# Game_Consol_Power.net
KiCad netlist of a schematic drawn in Altium Designer
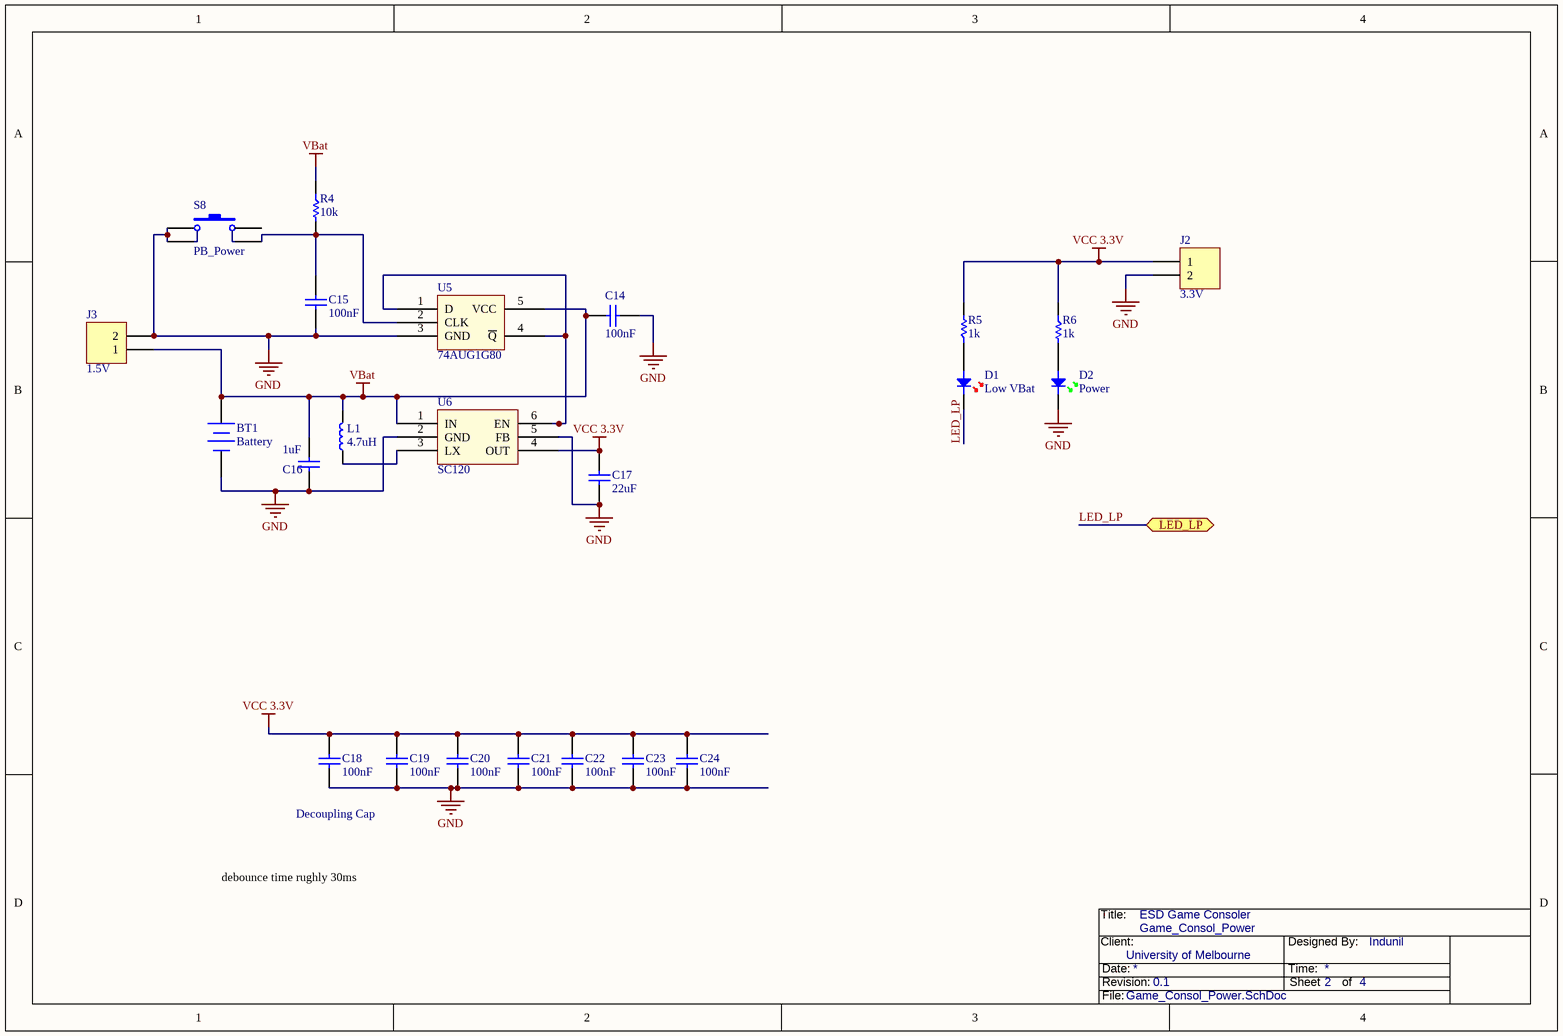
[diagram p0: Game_Consol_Power.SchDoc]

(export (version "E")
  (design (tool "Eeschema 10.0.6"))
  (components
    (comp (ref "BT1")
      (value "Battery")
      (footprint "BATT_HOLDER")
      (description "Multicell Battery")
      (fields (field (name "PUBLISHER") "Altium Limited"))
      (libsource (lib "Miscellaneous Devices") (part "Battery"))
    )
    (comp (ref "C14")
      (value "100nF")
      (footprint "0805")
      (description "Capacitor 100nF")
      (libsource (lib "EmbSD Lib 0v1") (part "C 0805"))
    )
    (comp (ref "C15")
      (value "100nF")
      (footprint "0805")
      (description "Capacitor 100nF")
      (libsource (lib "EmbSD Lib 0v1") (part "C 0805"))
    )
    (comp (ref "C16")
      (value "1uF")
      (footprint "0805")
      (description "Capacitor 100nF")
      (libsource (lib "EmbSD Lib 0v1") (part "C 0805"))
    )
    (comp (ref "C17")
      (value "22uF")
      (footprint "1210")
      (description "Capacitor 22uF")
      (fields
        (field (name "MANUFACTURER") "Generic Components")
        (field (name "MANUFACTURER PART NUMBER") "LMK316F226ZL-T")
        (field (name "PUBLISHER") "Altium Limited")
      )
      (libsource (lib "EmbSD Lib 0v1") (part "C 1210"))
    )
    (comp (ref "C18")
      (value "100nF")
      (footprint "0805")
      (description "Capacitor 100nF")
      (libsource (lib "EmbSD Lib 0v1") (part "C 0805"))
    )
    (comp (ref "C19")
      (value "100nF")
      (footprint "0805")
      (description "Capacitor 100nF")
      (libsource (lib "EmbSD Lib 0v1") (part "C 0805"))
    )
    (comp (ref "C20")
      (value "100nF")
      (footprint "0805")
      (description "Capacitor 100nF")
      (libsource (lib "EmbSD Lib 0v1") (part "C 0805"))
    )
    (comp (ref "C21")
      (value "100nF")
      (footprint "0805")
      (description "Capacitor 100nF")
      (libsource (lib "EmbSD Lib 0v1") (part "C 0805"))
    )
    (comp (ref "C22")
      (value "100nF")
      (footprint "0805")
      (description "Capacitor 100nF")
      (libsource (lib "EmbSD Lib 0v1") (part "C 0805"))
    )
    (comp (ref "C23")
      (value "100nF")
      (footprint "0805")
      (description "Capacitor 100nF")
      (libsource (lib "EmbSD Lib 0v1") (part "C 0805"))
    )
    (comp (ref "C24")
      (value "100nF")
      (footprint "0805")
      (description "Capacitor 100nF")
      (libsource (lib "EmbSD Lib 0v1") (part "C 0805"))
    )
    (comp (ref "D1")
      (value "Low VBat")
      (footprint "0805D")
      (description "Light Emitting Diode")
      (fields (field (name "MANUFACTURER") "Generic Components") (field (name "PUBLISHER") "Altium Limited"))
      (libsource (lib "EmbSD Lib 0v1") (part "LED RED"))
    )
    (comp (ref "D2")
      (value "Power")
      (footprint "0805D")
      (description "Light Emitting Diode")
      (fields (field (name "MANUFACTURER") "Generic Components") (field (name "PUBLISHER") "Altium Limited"))
      (libsource (lib "EmbSD Lib 0v1") (part "LED GREEN"))
    )
    (comp (ref "J2")
      (value "3.3V")
      (footprint "HDR1X2")
      (description "2 Pin Header")
      (fields (field (name "PUBLISHER") "Altium Limited"))
      (libsource (lib "") (part "HDR2_1"))
    )
    (comp (ref "J3")
      (value "1.5V")
      (footprint "HDR1X2")
      (description "2 Pin Header")
      (fields (field (name "PUBLISHER") "Altium Limited"))
      (libsource (lib "EmbSD Lib 0v1") (part "HDR2"))
    )
    (comp (ref "L1")
      (value "4.7uH")
      (footprint "1210L")
      (description "Inductor 4.7uH")
      (fields
        (field (name "MANUFACTURER") "Murata Electronics North America")
        (field (name "MANUFACTURER PART NUMBER") "LQH32CN4R7M23L")
        (field (name "PUBLISHER") "Altium Limited")
      )
      (libsource (lib "EmbSD Lib 0v1") (part "I 1210"))
    )
    (comp (ref "R4")
      (value "10k")
      (footprint "0805")
      (description "Resistor")
      (libsource (lib "EmbSD Lib 0v1") (part "R"))
    )
    (comp (ref "R5")
      (value "1k")
      (footprint "0805")
      (description "Resistor")
      (libsource (lib "EmbSD Lib 0v1") (part "R"))
    )
    (comp (ref "R6")
      (value "1k")
      (footprint "0805")
      (description "Resistor")
      (libsource (lib "EmbSD Lib 0v1") (part "R"))
    )
    (comp (ref "S8")
      (value "PB_Power")
      (footprint "SPNO_SMD")
      (description "Push Button Switch")
      (fields
        (field (name "MANUFACTURER") "TE Connectivity")
        (field (name "MANUFACTURER PART NUMBER") "FSM4JSMA")
        (field (name "PUBLISHER") "Altium Limited")
      )
      (libsource (lib "EmbSD Lib 0v1") (part "SW-PB"))
    )
    (comp (ref "U5")
      (value "74AUG1G80")
      (footprint "SOT23-5")
      (description "Inverted single D flip flop")
      (libsource (lib "EmbSD Lib 0v1") (part "74AUG1G80"))
    )
    (comp (ref "U6")
      (value "SC120")
      (footprint "SOT23-6")
      (description "Regulator Low Voltage")
      (libsource (lib "EmbSD Lib 0v1") (part "SC120"))
    )
  )
  (nets
    (net (code "1") (name "/LED_LP") (class "Default")
      (node (ref "D1") (pin "K") (pinfunction "K_K") (pintype "passive"))
    )
    (net (code "2") (name "GND") (class "Default")
      (node (ref "BT1") (pin "2") (pinfunction "-_2") (pintype "passive"))
      (node (ref "C14") (pin "1") (pinfunction "1_1") (pintype "passive"))
      (node (ref "C15") (pin "2") (pinfunction "2_2") (pintype "passive"))
      (node (ref "C16") (pin "2") (pinfunction "2_2") (pintype "passive"))
      (node (ref "C17") (pin "2") (pinfunction "2_2") (pintype "passive"))
      (node (ref "C18") (pin "2") (pinfunction "2_2") (pintype "passive"))
      (node (ref "C19") (pin "2") (pinfunction "2_2") (pintype "passive"))
      (node (ref "C20") (pin "2") (pinfunction "2_2") (pintype "passive"))
      (node (ref "C21") (pin "2") (pinfunction "2_2") (pintype "passive"))
      (node (ref "C22") (pin "2") (pinfunction "2_2") (pintype "passive"))
      (node (ref "C23") (pin "2") (pinfunction "2_2") (pintype "passive"))
      (node (ref "C24") (pin "2") (pinfunction "2_2") (pintype "passive"))
      (node (ref "D2") (pin "K") (pinfunction "K_K") (pintype "passive"))
      (node (ref "J2") (pin "2") (pinfunction "2_2") (pintype "passive"))
      (node (ref "J3") (pin "2") (pinfunction "2_2") (pintype "passive"))
      (node (ref "S8") (pin "1") (pinfunction "1_1") (pintype "passive"))
      (node (ref "S8") (pin "2") (pinfunction "2_2") (pintype "passive"))
      (node (ref "U5") (pin "3") (pinfunction "GND_3") (pintype "passive"))
      (node (ref "U6") (pin "2") (pinfunction "GND_2") (pintype "passive"))
      (node (ref "U6") (pin "5") (pinfunction "FB_5") (pintype "passive"))
    )
    (net (code "3") (name "Net-(D1-PadA)") (class "Default")
      (node (ref "D1") (pin "A") (pinfunction "A_A") (pintype "passive"))
      (node (ref "R5") (pin "1") (pintype "passive"))
    )
    (net (code "4") (name "Net-(D2-PadA)") (class "Default")
      (node (ref "D2") (pin "A") (pinfunction "A_A") (pintype "passive"))
      (node (ref "R6") (pin "2") (pintype "passive"))
    )
    (net (code "5") (name "Net-(U5-CLK)") (class "Default")
      (node (ref "C15") (pin "1") (pinfunction "1_1") (pintype "passive"))
      (node (ref "R4") (pin "2") (pintype "passive"))
      (node (ref "S8") (pin "4") (pinfunction "4_4") (pintype "passive"))
      (node (ref "U5") (pin "2") (pinfunction "CLK_2") (pintype "passive"))
    )
    (net (code "6") (name "Net-(U5-D)") (class "Default")
      (node (ref "U5") (pin "1") (pinfunction "D_1") (pintype "passive"))
      (node (ref "U5") (pin "4") (pinfunction "~{Q}_4") (pintype "passive"))
      (node (ref "U6") (pin "6") (pinfunction "EN_6") (pintype "passive"))
    )
    (net (code "7") (name "Net-(U6-LX)") (class "Default")
      (node (ref "L1") (pin "1") (pinfunction "1_1") (pintype "passive"))
      (node (ref "U6") (pin "3") (pinfunction "LX_3") (pintype "passive"))
    )
    (net (code "8") (name "VBat") (class "Default")
      (node (ref "BT1") (pin "1") (pinfunction "+_1") (pintype "passive"))
      (node (ref "C14") (pin "2") (pinfunction "2_2") (pintype "passive"))
      (node (ref "C16") (pin "1") (pinfunction "1_1") (pintype "passive"))
      (node (ref "J3") (pin "1") (pinfunction "1_1") (pintype "passive"))
      (node (ref "L1") (pin "2") (pinfunction "2_2") (pintype "passive"))
      (node (ref "R4") (pin "1") (pintype "passive"))
      (node (ref "U5") (pin "5") (pinfunction "VCC_5") (pintype "passive"))
      (node (ref "U6") (pin "1") (pinfunction "IN_1") (pintype "passive"))
    )
    (net (code "9") (name "VCC 3.3V") (class "Default")
      (node (ref "C17") (pin "1") (pinfunction "1_1") (pintype "passive"))
      (node (ref "C18") (pin "1") (pinfunction "1_1") (pintype "passive"))
      (node (ref "C19") (pin "1") (pinfunction "1_1") (pintype "passive"))
      (node (ref "C20") (pin "1") (pinfunction "1_1") (pintype "passive"))
      (node (ref "C21") (pin "1") (pinfunction "1_1") (pintype "passive"))
      (node (ref "C22") (pin "1") (pinfunction "1_1") (pintype "passive"))
      (node (ref "C23") (pin "1") (pinfunction "1_1") (pintype "passive"))
      (node (ref "C24") (pin "1") (pinfunction "1_1") (pintype "passive"))
      (node (ref "J2") (pin "1") (pinfunction "1_1") (pintype "passive"))
      (node (ref "R5") (pin "2") (pintype "passive"))
      (node (ref "R6") (pin "1") (pintype "passive"))
      (node (ref "U6") (pin "4") (pinfunction "OUT_4") (pintype "passive"))
    )
    (net (code "10") (name "unconnected-(S8-Pad3)") (class "Default")
      (node (ref "S8") (pin "3") (pinfunction "3_3") (pintype "passive"))
    )
  )
)
